# PlugEVSE_2x20A.net
KiCad netlist of a schematic drawn in EAGLE
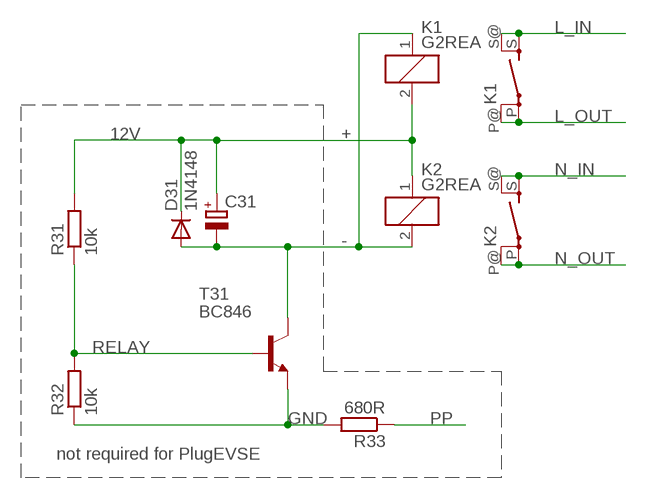
[diagram p0: schematic, sheet 1]

(export (version "E")
  (design (tool "Eeschema 10.0.6"))
  (components
    (comp (ref "C31")
      (value "CPOL-EUSMCC")
      (footprint "eagle-import:SMC_C")
      (libsource (lib "eagle-import") (part "CPOL-EUSMCC"))
    )
    (comp (ref "D31")
      (value "1N4148")
      (footprint "eagle-import:SOD123")
      (libsource (lib "eagle-import") (part "DIODE-SOD123"))
    )
    (comp (ref "K1")
      (value "G2REA")
      (footprint "eagle-import:G2REA")
      (libsource (lib "eagle-import") (part "G2REA"))
    )
    (comp (ref "K2")
      (value "G2REA")
      (footprint "eagle-import:G2REA")
      (libsource (lib "eagle-import") (part "G2REA"))
    )
    (comp (ref "R31")
      (value "10k")
      (footprint "eagle-import:R0603")
      (libsource (lib "eagle-import") (part "rcl_334_R-EU_R0603"))
    )
    (comp (ref "R32")
      (value "10k")
      (footprint "eagle-import:R0603")
      (libsource (lib "eagle-import") (part "rcl_334_R-EU_R0603"))
    )
    (comp (ref "R33")
      (value "680R")
      (footprint "eagle-import:R2512")
      (libsource (lib "eagle-import") (part "R-EU_R2512"))
    )
    (comp (ref "T31")
      (value "BC846")
      (footprint "eagle-import:SOT23")
      (libsource (lib "eagle-import") (part "BC846"))
    )
  )
  (nets
    (net (code "1") (name "/12V") (class "Default")
      (node (ref "C31") (pin "+") (pinfunction "+_+") (pintype "passive"))
      (node (ref "D31") (pin "C") (pinfunction "C_C") (pintype "passive"))
      (node (ref "K1") (pin "2") (pinfunction "2_2") (pintype "passive"))
      (node (ref "K2") (pin "1") (pinfunction "1_1") (pintype "passive"))
      (node (ref "R31") (pin "2") (pinfunction "2_2") (pintype "passive"))
    )
    (net (code "2") (name "/GND") (class "Default")
      (node (ref "R32") (pin "1") (pinfunction "1_1") (pintype "passive"))
      (node (ref "R33") (pin "2") (pinfunction "2_2") (pintype "passive"))
      (node (ref "T31") (pin "2") (pinfunction "E_2") (pintype "passive"))
    )
    (net (code "3") (name "/L_IN") (class "Default")
      (node (ref "K1") (pin "S") (pinfunction "S_S") (pintype "passive"))
      (node (ref "K1") (pin "S@") (pinfunction "S_S@") (pintype "passive"))
    )
    (net (code "4") (name "/L_OUT") (class "Default")
      (node (ref "K1") (pin "P") (pinfunction "P_P") (pintype "passive"))
      (node (ref "K1") (pin "P@") (pinfunction "P_P@") (pintype "passive"))
    )
    (net (code "5") (name "/N_IN") (class "Default")
      (node (ref "K2") (pin "S") (pinfunction "S_S") (pintype "passive"))
      (node (ref "K2") (pin "S@") (pinfunction "S_S@") (pintype "passive"))
    )
    (net (code "6") (name "/N_OUT") (class "Default")
      (node (ref "K2") (pin "P") (pinfunction "P_P") (pintype "passive"))
      (node (ref "K2") (pin "P@") (pinfunction "P_P@") (pintype "passive"))
    )
    (net (code "7") (name "/PP") (class "Default")
      (node (ref "R33") (pin "1") (pinfunction "1_1") (pintype "passive"))
    )
    (net (code "8") (name "/RELAY") (class "Default")
      (node (ref "R31") (pin "1") (pinfunction "1_1") (pintype "passive"))
      (node (ref "R32") (pin "2") (pinfunction "2_2") (pintype "passive"))
      (node (ref "T31") (pin "1") (pinfunction "B_1") (pintype "passive"))
    )
    (net (code "9") (name "Net-(T31-C)") (class "Default")
      (node (ref "C31") (pin "-") (pinfunction "-_-") (pintype "passive"))
      (node (ref "D31") (pin "A") (pinfunction "A_A") (pintype "passive"))
      (node (ref "K1") (pin "1") (pinfunction "1_1") (pintype "passive"))
      (node (ref "K2") (pin "2") (pinfunction "2_2") (pintype "passive"))
      (node (ref "T31") (pin "3") (pinfunction "C_3") (pintype "passive"))
    )
  )
)
